# ArduSensor-Phototransistor.net
KiCad netlist of a schematic drawn in EAGLE
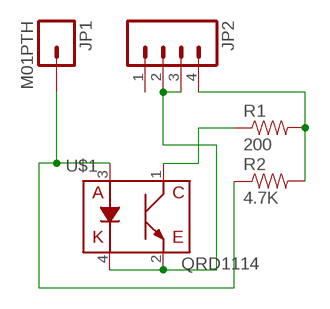
[diagram p0: schematic, sheet 1]

(export (version "E")
  (design (tool "Eeschema 10.0.6"))
  (components
    (comp (ref "JP1")
      (value "M01PTH")
      (footprint "eagle-import:1X01")
      (libsource (lib "eagle-import") (part "M01PTH"))
    )
    (comp (ref "JP2")
      (value "M04PTH")
      (footprint "eagle-import:1X04")
      (libsource (lib "eagle-import") (part "M04PTH"))
    )
    (comp (ref "R1")
      (value "200")
      (footprint "eagle-import:AXIAL-0.3")
      (libsource (lib "eagle-import") (part "RESISTORAXIAL-0.3"))
    )
    (comp (ref "R2")
      (value "4.7K")
      (footprint "eagle-import:AXIAL-0.3")
      (libsource (lib "eagle-import") (part "RESISTORAXIAL-0.3"))
    )
    (comp (ref "U$1")
      (value "QRD1114")
      (footprint "eagle-import:QRD1114")
      (libsource (lib "eagle-import") (part "QRD1114"))
    )
  )
  (nets
    (net (code "1") (name "Net-(R1-1)") (class "Default")
      (node (ref "R1") (pin "P$1") (pinfunction "1_P$1") (pintype "passive"))
      (node (ref "U$1") (pin "1") (pinfunction "E_1") (pintype "bidirectional"))
    )
    (net (code "2") (name "Net-(R1-2)") (class "Default")
      (node (ref "JP2") (pin "4") (pinfunction "4_4") (pintype "passive"))
      (node (ref "R1") (pin "P$2") (pinfunction "2_P$2") (pintype "passive"))
      (node (ref "R2") (pin "P$2") (pinfunction "2_P$2") (pintype "passive"))
    )
    (net (code "3") (name "Net-(R2-1)") (class "Default")
      (node (ref "JP1") (pin "1") (pinfunction "1_1") (pintype "passive"))
      (node (ref "R2") (pin "P$1") (pinfunction "1_P$1") (pintype "passive"))
      (node (ref "U$1") (pin "3") (pinfunction "A_3") (pintype "bidirectional"))
    )
    (net (code "4") (name "Net-(U$1-C)") (class "Default")
      (node (ref "JP2") (pin "2") (pinfunction "2_2") (pintype "passive"))
      (node (ref "JP2") (pin "3") (pinfunction "3_3") (pintype "passive"))
      (node (ref "U$1") (pin "2") (pinfunction "C_2") (pintype "bidirectional"))
      (node (ref "U$1") (pin "4") (pinfunction "K_4") (pintype "bidirectional"))
    )
    (net (code "5") (name "unconnected-(JP2-Pad1)") (class "Default")
      (node (ref "JP2") (pin "1") (pinfunction "1_1") (pintype "passive"))
    )
  )
)
